# 0_2.net
KiCad netlist of a schematic drawn in EAGLE
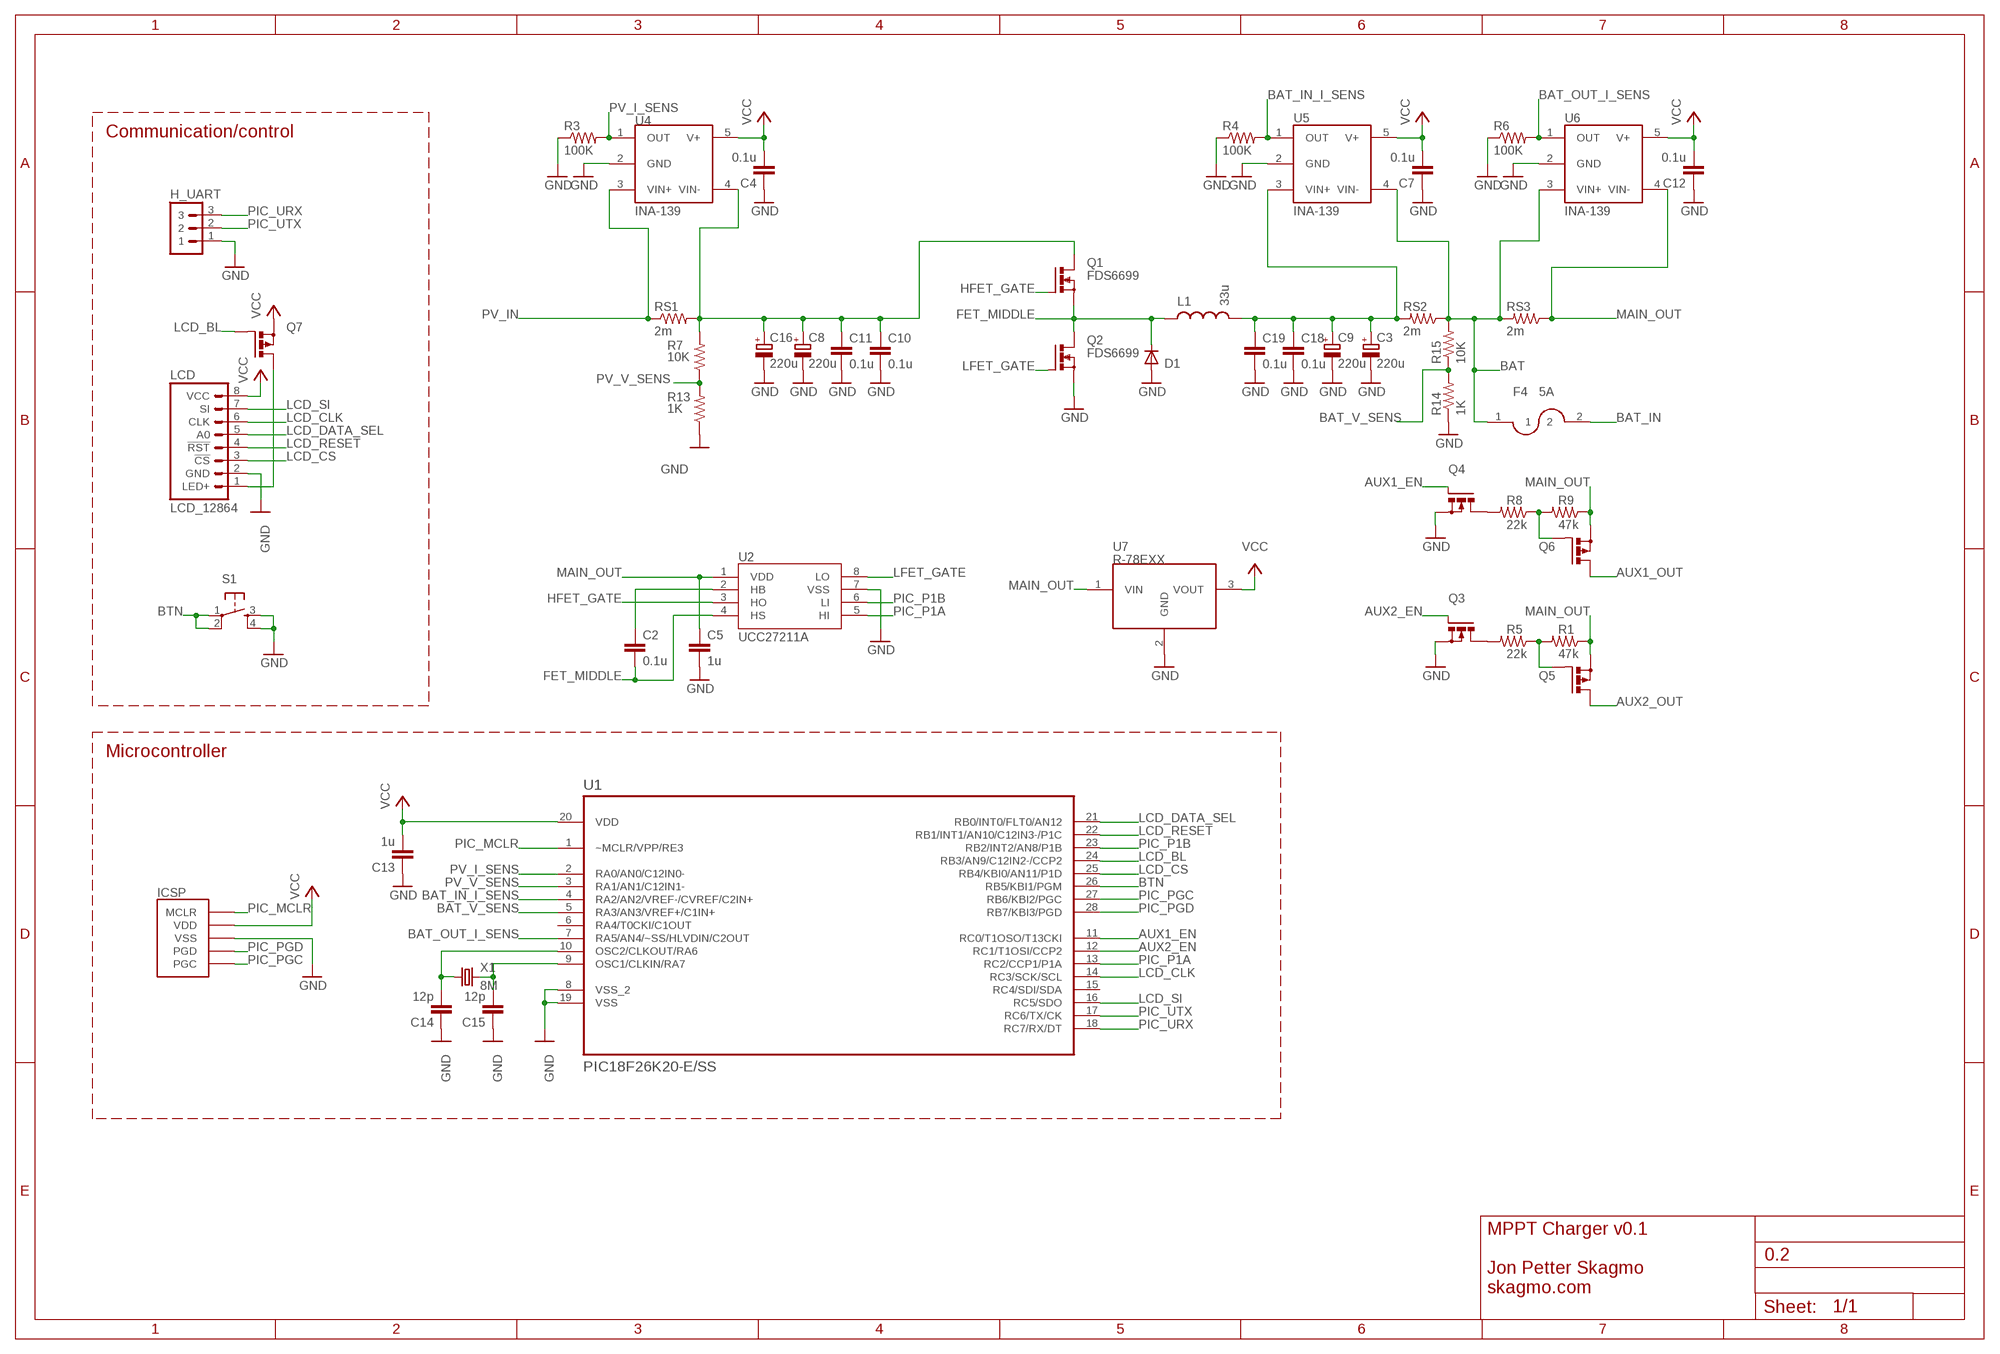
[diagram p0: schematic, sheet 1]

(export (version "E")
  (design (tool "Eeschema 10.0.6"))
  (components
    (comp (ref "C2")
      (value "0.1u")
      (footprint "eagle-import:0603")
      (libsource (lib "eagle-import") (part "CAP0603"))
    )
    (comp (ref "C3")
      (value "220u")
      (footprint "eagle-import:E3,5-8")
      (fields (field (name "PARTNO") "35ZLH220MEFC8X11.5"))
      (libsource (lib "eagle-import") (part "CPOL-EUE3.5-8"))
    )
    (comp (ref "C4")
      (value "0.1u")
      (footprint "eagle-import:0603")
      (libsource (lib "eagle-import") (part "CAP0603"))
    )
    (comp (ref "C5")
      (value "1u")
      (footprint "eagle-import:0603")
      (libsource (lib "eagle-import") (part "CAP0603"))
    )
    (comp (ref "C7")
      (value "0.1u")
      (footprint "eagle-import:0603")
      (libsource (lib "eagle-import") (part "CAP0603"))
    )
    (comp (ref "C8")
      (value "220u")
      (footprint "eagle-import:E3,5-8")
      (fields (field (name "PARTNO") "35ZLH220MEFC8X11.5"))
      (libsource (lib "eagle-import") (part "CPOL-EUE3.5-8"))
    )
    (comp (ref "C9")
      (value "220u")
      (footprint "eagle-import:E3,5-8")
      (fields (field (name "PARTNO") "35ZLH220MEFC8X11.5"))
      (libsource (lib "eagle-import") (part "CPOL-EUE3.5-8"))
    )
    (comp (ref "C10")
      (value "0.1u")
      (footprint "eagle-import:0603")
      (libsource (lib "eagle-import") (part "CAP0603"))
    )
    (comp (ref "C11")
      (value "0.1u")
      (footprint "eagle-import:0603")
      (libsource (lib "eagle-import") (part "CAP0603"))
    )
    (comp (ref "C12")
      (value "0.1u")
      (footprint "eagle-import:0603")
      (libsource (lib "eagle-import") (part "CAP0603"))
    )
    (comp (ref "C13")
      (value "1u")
      (footprint "eagle-import:0603")
      (libsource (lib "eagle-import") (part "CAP0603"))
    )
    (comp (ref "C14")
      (value "12p")
      (footprint "eagle-import:0603")
      (libsource (lib "eagle-import") (part "CAP0603"))
    )
    (comp (ref "C15")
      (value "12p")
      (footprint "eagle-import:0603")
      (libsource (lib "eagle-import") (part "CAP0603"))
    )
    (comp (ref "C16")
      (value "220u")
      (footprint "eagle-import:E3,5-8")
      (fields (field (name "PARTNO") "35ZLH220MEFC8X11.5"))
      (libsource (lib "eagle-import") (part "CPOL-EUE3.5-8"))
    )
    (comp (ref "C18")
      (value "0.1u")
      (footprint "eagle-import:0603")
      (libsource (lib "eagle-import") (part "CAP0603"))
    )
    (comp (ref "C19")
      (value "0.1u")
      (footprint "eagle-import:0603")
      (libsource (lib "eagle-import") (part "CAP0603"))
    )
    (comp (ref "D1")
      (value "DIODESMB")
      (footprint "eagle-import:SMB-DIODE")
      (fields (field (name "PARTNO") "SK54B-LTP"))
      (libsource (lib "eagle-import") (part "DIODESMB"))
    )
    (comp (ref "F4")
      (value "5A")
      (footprint "eagle-import:1206")
      (fields (field (name "PARTNO") "C1T 5"))
      (libsource (lib "eagle-import") (part "FUSE1206"))
    )
    (comp (ref "H_UART")
      (value "H1X3_XH")
      (footprint "eagle-import:CON_B3B-XH-A")
      (fields (field (name "PARTNO") "B3B-XH-A (LF)(SN)(P)"))
      (libsource (lib "eagle-import") (part "H1X3_XH"))
    )
    (comp (ref "ICSP")
      (value "1X5_ICSP")
      (footprint "eagle-import:1X5_2MM")
      (libsource (lib "eagle-import") (part "1X5_ICSP"))
    )
    (comp (ref "L1")
      (value "33u")
      (footprint "eagle-import:IHLP-6767")
      (fields (field (name "PARTNO") "IHLP6767GZER330M11"))
      (libsource (lib "eagle-import") (part "INDUCTORIHLP-6767"))
    )
    (comp (ref "LCD")
      (value "LCD_12864")
      (footprint "eagle-import:LCD_12864")
      (libsource (lib "eagle-import") (part "LCD_12864"))
    )
    (comp (ref "Q1")
      (value "FDS6699")
      (footprint "eagle-import:SO08")
      (fields (field (name "PARTNO") "SI4128DY-T1-GE3"))
      (libsource (lib "eagle-import") (part "PMOSFET_N"))
    )
    (comp (ref "Q2")
      (value "FDS6699")
      (footprint "eagle-import:SO08")
      (fields (field (name "PARTNO") "SI4128DY-T1-GE3"))
      (libsource (lib "eagle-import") (part "PMOSFET_N"))
    )
    (comp (ref "Q3")
      (value "MOSFET_N_SOT23-3")
      (footprint "eagle-import:SOT23-3")
      (fields (field (name "PARTNO") "BSH103,215"))
      (libsource (lib "eagle-import") (part "MOSFET_N_SOT23-3"))
    )
    (comp (ref "Q4")
      (value "MOSFET_N_SOT23-3")
      (footprint "eagle-import:SOT23-3")
      (fields (field (name "PARTNO") "BSH103,215"))
      (libsource (lib "eagle-import") (part "MOSFET_N_SOT23-3"))
    )
    (comp (ref "Q5")
      (value "PMOSFET_P")
      (footprint "eagle-import:SO08")
      (fields (field (name "PARTNO") "FDS6681Z"))
      (libsource (lib "eagle-import") (part "PMOSFET_P"))
    )
    (comp (ref "Q6")
      (value "PMOSFET_P")
      (footprint "eagle-import:SO08")
      (fields (field (name "PARTNO") "FDS6681Z"))
      (libsource (lib "eagle-import") (part "PMOSFET_P"))
    )
    (comp (ref "Q7")
      (value "MOSFET_P_SOT23")
      (footprint "eagle-import:SOT23-3")
      (libsource (lib "eagle-import") (part "MOSFET_P_SOT23"))
    )
    (comp (ref "R1")
      (value "47k")
      (footprint "eagle-import:0603")
      (libsource (lib "eagle-import") (part "RESISTOR0603"))
    )
    (comp (ref "R3")
      (value "100K")
      (footprint "eagle-import:0603")
      (libsource (lib "eagle-import") (part "RESISTOR0603"))
    )
    (comp (ref "R4")
      (value "100K")
      (footprint "eagle-import:0603")
      (libsource (lib "eagle-import") (part "RESISTOR0603"))
    )
    (comp (ref "R5")
      (value "22k")
      (footprint "eagle-import:0603")
      (libsource (lib "eagle-import") (part "RESISTOR0603"))
    )
    (comp (ref "R6")
      (value "100K")
      (footprint "eagle-import:0603")
      (libsource (lib "eagle-import") (part "RESISTOR0603"))
    )
    (comp (ref "R7")
      (value "10K")
      (footprint "eagle-import:0603")
      (libsource (lib "eagle-import") (part "RESISTOR0603"))
    )
    (comp (ref "R8")
      (value "22k")
      (footprint "eagle-import:0603")
      (libsource (lib "eagle-import") (part "RESISTOR0603"))
    )
    (comp (ref "R9")
      (value "47k")
      (footprint "eagle-import:0603")
      (libsource (lib "eagle-import") (part "RESISTOR0603"))
    )
    (comp (ref "R13")
      (value "1K")
      (footprint "eagle-import:0603")
      (libsource (lib "eagle-import") (part "RESISTOR0603"))
    )
    (comp (ref "R14")
      (value "1K")
      (footprint "eagle-import:0603")
      (libsource (lib "eagle-import") (part "RESISTOR0603"))
    )
    (comp (ref "R15")
      (value "10K")
      (footprint "eagle-import:0603")
      (libsource (lib "eagle-import") (part "RESISTOR0603"))
    )
    (comp (ref "RS1")
      (value "2m")
      (footprint "eagle-import:R3225")
      (fields (field (name "PARTNO") "PMR25HZPFV2L00"))
      (libsource (lib "eagle-import") (part "R-US_R3225"))
    )
    (comp (ref "RS2")
      (value "2m")
      (footprint "eagle-import:R3225")
      (fields (field (name "PARTNO") "PMR25HZPFV2L00"))
      (libsource (lib "eagle-import") (part "R-US_R3225"))
    )
    (comp (ref "RS3")
      (value "2m")
      (footprint "eagle-import:R3225")
      (fields (field (name "PARTNO") "PMR25HZPFV2L00"))
      (libsource (lib "eagle-import") (part "R-US_R3225"))
    )
    (comp (ref "S1")
      (value "TAC_SWITCH")
      (footprint "eagle-import:SWITCH_B3FS-1002P")
      (libsource (lib "eagle-import") (part "TAC_SWITCH"))
    )
    (comp (ref "U1")
      (value "PIC18F26K20-E/SS")
      (footprint "eagle-import:SOP65P780X200-28N")
      (fields (field (name "PARTNO") "PIC18F26K22-I/SS"))
      (libsource (lib "eagle-import") (part "PIC18F26K20-E/SS"))
    )
    (comp (ref "U2")
      (value "UCC27211A")
      (footprint "eagle-import:SO08")
      (fields (field (name "PARTNO") "UCC27211D"))
      (libsource (lib "eagle-import") (part "UCC27211A"))
    )
    (comp (ref "U4")
      (value "INA-139")
      (footprint "eagle-import:SOT23-5")
      (fields (field (name "PARTNO") "INA139NA/250"))
      (libsource (lib "eagle-import") (part "INA-169"))
    )
    (comp (ref "U5")
      (value "INA-139")
      (footprint "eagle-import:SOT23-5")
      (fields (field (name "PARTNO") "INA139NA/250"))
      (libsource (lib "eagle-import") (part "INA-169"))
    )
    (comp (ref "U6")
      (value "INA-139")
      (footprint "eagle-import:SOT23-5")
      (fields (field (name "PARTNO") "INA139NA/250"))
      (libsource (lib "eagle-import") (part "INA-169"))
    )
    (comp (ref "U7")
      (value "R-78EXX")
      (footprint "eagle-import:R-78EXX")
      (fields (field (name "PARTNO") "R-78E3.3-0.5"))
      (libsource (lib "eagle-import") (part "R-78EXX"))
    )
    (comp (ref "X1")
      (value "8M")
      (footprint "eagle-import:TXC-7A")
      (fields (field (name "PARTNO") "7A-8.000MAAE-T"))
      (libsource (lib "eagle-import") (part "TXC-7A"))
    )
  )
  (nets
    (net (code "1") (name "/AUX1_EN") (class "Default")
      (node (ref "Q4") (pin "1") (pinfunction "G_1") (pintype "passive"))
      (node (ref "U1") (pin "11") (pinfunction "RC0/T1OSO/T13CKI_11") (pintype "bidirectional"))
    )
    (net (code "2") (name "/AUX1_OUT") (class "Default")
      (node (ref "Q6") (pin "5") (pinfunction "D_5") (pintype "passive"))
      (node (ref "Q6") (pin "6") (pinfunction "D_6") (pintype "passive"))
      (node (ref "Q6") (pin "7") (pinfunction "D_7") (pintype "passive"))
      (node (ref "Q6") (pin "8") (pinfunction "D_8") (pintype "passive"))
    )
    (net (code "3") (name "/AUX2_EN") (class "Default")
      (node (ref "Q3") (pin "1") (pinfunction "G_1") (pintype "passive"))
      (node (ref "U1") (pin "12") (pinfunction "RC1/T1OSI/CCP2_12") (pintype "bidirectional"))
    )
    (net (code "4") (name "/AUX2_OUT") (class "Default")
      (node (ref "Q5") (pin "5") (pinfunction "D_5") (pintype "passive"))
      (node (ref "Q5") (pin "6") (pinfunction "D_6") (pintype "passive"))
      (node (ref "Q5") (pin "7") (pinfunction "D_7") (pintype "passive"))
      (node (ref "Q5") (pin "8") (pinfunction "D_8") (pintype "passive"))
    )
    (net (code "5") (name "/BAT") (class "Default")
      (node (ref "F4") (pin "1") (pinfunction "1_1") (pintype "bidirectional"))
      (node (ref "R15") (pin "2") (pinfunction "2_2") (pintype "passive"))
      (node (ref "RS2") (pin "1") (pinfunction "1_1") (pintype "passive"))
      (node (ref "RS3") (pin "2") (pinfunction "2_2") (pintype "passive"))
      (node (ref "U5") (pin "4") (pinfunction "VIN-_4") (pintype "bidirectional"))
      (node (ref "U6") (pin "3") (pinfunction "VIN+_3") (pintype "bidirectional"))
    )
    (net (code "6") (name "/BAT_IN") (class "Default")
      (node (ref "F4") (pin "2") (pinfunction "2_2") (pintype "bidirectional"))
    )
    (net (code "7") (name "/BAT_IN_I_SENS") (class "Default")
      (node (ref "R4") (pin "2") (pinfunction "2_2") (pintype "passive"))
      (node (ref "U1") (pin "4") (pinfunction "RA2/AN2/VREF-/CVREF/C2IN+_4") (pintype "bidirectional"))
      (node (ref "U5") (pin "1") (pinfunction "OUT_1") (pintype "bidirectional"))
    )
    (net (code "8") (name "/BAT_OUT_I_SENS") (class "Default")
      (node (ref "R6") (pin "2") (pinfunction "2_2") (pintype "passive"))
      (node (ref "U1") (pin "7") (pinfunction "RA5/AN4/~{SS/HLVDIN/C2OUT}_7") (pintype "bidirectional"))
      (node (ref "U6") (pin "1") (pinfunction "OUT_1") (pintype "bidirectional"))
    )
    (net (code "9") (name "/BAT_V_SENS") (class "Default")
      (node (ref "R14") (pin "2") (pinfunction "2_2") (pintype "passive"))
      (node (ref "R15") (pin "1") (pinfunction "1_1") (pintype "passive"))
      (node (ref "U1") (pin "5") (pinfunction "RA3/AN3/VREF+/C1IN+_5") (pintype "bidirectional"))
    )
    (net (code "10") (name "/BTN") (class "Default")
      (node (ref "S1") (pin "1") (pinfunction "1_1") (pintype "passive"))
      (node (ref "S1") (pin "2") (pinfunction "2_2") (pintype "passive"))
      (node (ref "U1") (pin "26") (pinfunction "RB5/KBI1/PGM_26") (pintype "bidirectional"))
    )
    (net (code "11") (name "/FET_MIDDLE") (class "Default")
      (node (ref "C2") (pin "2") (pinfunction "2_2") (pintype "passive"))
      (node (ref "D1") (pin "C") (pinfunction "C_C") (pintype "passive"))
      (node (ref "L1") (pin "P$1") (pinfunction "1_P$1") (pintype "passive"))
      (node (ref "Q1") (pin "1") (pinfunction "S_1") (pintype "passive"))
      (node (ref "Q1") (pin "2") (pinfunction "S_2") (pintype "passive"))
      (node (ref "Q1") (pin "3") (pinfunction "S_3") (pintype "passive"))
      (node (ref "Q2") (pin "5") (pinfunction "D_5") (pintype "passive"))
      (node (ref "Q2") (pin "6") (pinfunction "D_6") (pintype "passive"))
      (node (ref "Q2") (pin "7") (pinfunction "D_7") (pintype "passive"))
      (node (ref "Q2") (pin "8") (pinfunction "D_8") (pintype "passive"))
      (node (ref "U2") (pin "4") (pinfunction "HS_4") (pintype "bidirectional"))
    )
    (net (code "12") (name "/HFET_GATE") (class "Default")
      (node (ref "Q1") (pin "4") (pinfunction "G_4") (pintype "passive"))
      (node (ref "U2") (pin "3") (pinfunction "HO_3") (pintype "bidirectional"))
    )
    (net (code "13") (name "/LCD_BL") (class "Default")
      (node (ref "Q7") (pin "1") (pinfunction "G_1") (pintype "passive"))
      (node (ref "U1") (pin "24") (pinfunction "RB3/AN9/C12IN2-/CCP2_24") (pintype "bidirectional"))
    )
    (net (code "14") (name "/LCD_CLK") (class "Default")
      (node (ref "LCD") (pin "6") (pinfunction "CLK_6") (pintype "passive"))
      (node (ref "U1") (pin "14") (pinfunction "RC3/SCK/SCL_14") (pintype "bidirectional"))
    )
    (net (code "15") (name "/LCD_CS") (class "Default")
      (node (ref "LCD") (pin "3") (pinfunction "~{CS}_3") (pintype "passive"))
      (node (ref "U1") (pin "25") (pinfunction "RB4/KBI0/AN11/P1D_25") (pintype "bidirectional"))
    )
    (net (code "16") (name "/LCD_DATA_SEL") (class "Default")
      (node (ref "LCD") (pin "5") (pinfunction "A0_5") (pintype "passive"))
      (node (ref "U1") (pin "21") (pinfunction "RB0/INT0/FLT0/AN12_21") (pintype "bidirectional"))
    )
    (net (code "17") (name "/LCD_RESET") (class "Default")
      (node (ref "LCD") (pin "4") (pinfunction "~{RST}_4") (pintype "passive"))
      (node (ref "U1") (pin "22") (pinfunction "RB1/INT1/AN10/C12IN3-/P1C_22") (pintype "bidirectional"))
    )
    (net (code "18") (name "/LCD_SI") (class "Default")
      (node (ref "LCD") (pin "7") (pinfunction "SI_7") (pintype "passive"))
      (node (ref "U1") (pin "16") (pinfunction "RC5/SDO_16") (pintype "bidirectional"))
    )
    (net (code "19") (name "/LFET_GATE") (class "Default")
      (node (ref "Q2") (pin "4") (pinfunction "G_4") (pintype "passive"))
      (node (ref "U2") (pin "8") (pinfunction "LO_8") (pintype "bidirectional"))
    )
    (net (code "20") (name "/MAIN_OUT") (class "Default")
      (node (ref "C5") (pin "1") (pinfunction "1_1") (pintype "passive"))
      (node (ref "Q5") (pin "1") (pinfunction "S_1") (pintype "passive"))
      (node (ref "Q5") (pin "2") (pinfunction "S_2") (pintype "passive"))
      (node (ref "Q5") (pin "3") (pinfunction "S_3") (pintype "passive"))
      (node (ref "Q6") (pin "1") (pinfunction "S_1") (pintype "passive"))
      (node (ref "Q6") (pin "2") (pinfunction "S_2") (pintype "passive"))
      (node (ref "Q6") (pin "3") (pinfunction "S_3") (pintype "passive"))
      (node (ref "R1") (pin "1") (pinfunction "1_1") (pintype "passive"))
      (node (ref "R9") (pin "1") (pinfunction "1_1") (pintype "passive"))
      (node (ref "RS3") (pin "1") (pinfunction "1_1") (pintype "passive"))
      (node (ref "U2") (pin "1") (pinfunction "VDD_1") (pintype "bidirectional"))
      (node (ref "U6") (pin "4") (pinfunction "VIN-_4") (pintype "bidirectional"))
      (node (ref "U7") (pin "1") (pinfunction "VIN_1") (pintype "bidirectional"))
    )
    (net (code "21") (name "/PIC_MCLR") (class "Default")
      (node (ref "ICSP") (pin "P$1") (pinfunction "MCLR_P$1") (pintype "bidirectional"))
      (node (ref "U1") (pin "1") (pinfunction "~{MCLR/VPP/RE3}_1") (pintype "input"))
    )
    (net (code "22") (name "/PIC_P1A") (class "Default")
      (node (ref "U1") (pin "13") (pinfunction "RC2/CCP1/P1A_13") (pintype "bidirectional"))
      (node (ref "U2") (pin "5") (pinfunction "HI_5") (pintype "bidirectional"))
    )
    (net (code "23") (name "/PIC_P1B") (class "Default")
      (node (ref "U1") (pin "23") (pinfunction "RB2/INT2/AN8/P1B_23") (pintype "bidirectional"))
      (node (ref "U2") (pin "6") (pinfunction "LI_6") (pintype "bidirectional"))
    )
    (net (code "24") (name "/PIC_PGC") (class "Default")
      (node (ref "ICSP") (pin "P$5") (pinfunction "PGC_P$5") (pintype "bidirectional"))
      (node (ref "U1") (pin "27") (pinfunction "RB6/KBI2/PGC_27") (pintype "bidirectional"))
    )
    (net (code "25") (name "/PIC_PGD") (class "Default")
      (node (ref "ICSP") (pin "P$4") (pinfunction "PGD_P$4") (pintype "bidirectional"))
      (node (ref "U1") (pin "28") (pinfunction "RB7/KBI3/PGD_28") (pintype "bidirectional"))
    )
    (net (code "26") (name "/PIC_URX") (class "Default")
      (node (ref "H_UART") (pin "3") (pinfunction "3_3") (pintype "passive"))
      (node (ref "U1") (pin "18") (pinfunction "RC7/RX/DT_18") (pintype "bidirectional"))
    )
    (net (code "27") (name "/PIC_UTX") (class "Default")
      (node (ref "H_UART") (pin "2") (pinfunction "2_2") (pintype "passive"))
      (node (ref "U1") (pin "17") (pinfunction "RC6/TX/CK_17") (pintype "bidirectional"))
    )
    (net (code "28") (name "/PV_IN") (class "Default")
      (node (ref "RS1") (pin "1") (pinfunction "1_1") (pintype "passive"))
      (node (ref "U4") (pin "3") (pinfunction "VIN+_3") (pintype "bidirectional"))
    )
    (net (code "29") (name "/PV_I_SENS") (class "Default")
      (node (ref "R3") (pin "2") (pinfunction "2_2") (pintype "passive"))
      (node (ref "U1") (pin "2") (pinfunction "RA0/AN0/C12IN0-_2") (pintype "bidirectional"))
      (node (ref "U4") (pin "1") (pinfunction "OUT_1") (pintype "bidirectional"))
    )
    (net (code "30") (name "/PV_V_SENS") (class "Default")
      (node (ref "R13") (pin "2") (pinfunction "2_2") (pintype "passive"))
      (node (ref "R7") (pin "1") (pinfunction "1_1") (pintype "passive"))
      (node (ref "U1") (pin "3") (pinfunction "RA1/AN1/C12IN1-_3") (pintype "bidirectional"))
    )
    (net (code "31") (name "GND") (class "Default")
      (node (ref "C10") (pin "2") (pinfunction "2_2") (pintype "passive"))
      (node (ref "C11") (pin "2") (pinfunction "2_2") (pintype "passive"))
      (node (ref "C12") (pin "1") (pinfunction "1_1") (pintype "passive"))
      (node (ref "C13") (pin "1") (pinfunction "1_1") (pintype "passive"))
      (node (ref "C14") (pin "1") (pinfunction "1_1") (pintype "passive"))
      (node (ref "C15") (pin "1") (pinfunction "1_1") (pintype "passive"))
      (node (ref "C16") (pin "-") (pinfunction "-_-") (pintype "passive"))
      (node (ref "C18") (pin "2") (pinfunction "2_2") (pintype "passive"))
      (node (ref "C19") (pin "2") (pinfunction "2_2") (pintype "passive"))
      (node (ref "C3") (pin "-") (pinfunction "-_-") (pintype "passive"))
      (node (ref "C4") (pin "1") (pinfunction "1_1") (pintype "passive"))
      (node (ref "C5") (pin "2") (pinfunction "2_2") (pintype "passive"))
      (node (ref "C7") (pin "1") (pinfunction "1_1") (pintype "passive"))
      (node (ref "C8") (pin "-") (pinfunction "-_-") (pintype "passive"))
      (node (ref "C9") (pin "-") (pinfunction "-_-") (pintype "passive"))
      (node (ref "D1") (pin "A") (pinfunction "A_A") (pintype "passive"))
      (node (ref "H_UART") (pin "1") (pinfunction "1_1") (pintype "passive"))
      (node (ref "ICSP") (pin "P$3") (pinfunction "VSS_P$3") (pintype "power_in"))
      (node (ref "LCD") (pin "2") (pinfunction "GND_2") (pintype "passive"))
      (node (ref "Q2") (pin "1") (pinfunction "S_1") (pintype "passive"))
      (node (ref "Q2") (pin "2") (pinfunction "S_2") (pintype "passive"))
      (node (ref "Q2") (pin "3") (pinfunction "S_3") (pintype "passive"))
      (node (ref "Q3") (pin "2") (pinfunction "S_2") (pintype "passive"))
      (node (ref "Q4") (pin "2") (pinfunction "S_2") (pintype "passive"))
      (node (ref "R13") (pin "1") (pinfunction "1_1") (pintype "passive"))
      (node (ref "R14") (pin "1") (pinfunction "1_1") (pintype "passive"))
      (node (ref "R3") (pin "1") (pinfunction "1_1") (pintype "passive"))
      (node (ref "R4") (pin "1") (pinfunction "1_1") (pintype "passive"))
      (node (ref "R6") (pin "1") (pinfunction "1_1") (pintype "passive"))
      (node (ref "S1") (pin "3") (pinfunction "3_3") (pintype "passive"))
      (node (ref "S1") (pin "4") (pinfunction "4_4") (pintype "passive"))
      (node (ref "U1") (pin "19") (pinfunction "VSS_19") (pintype "power_in"))
      (node (ref "U1") (pin "8") (pinfunction "VSS_2_8") (pintype "power_in"))
      (node (ref "U2") (pin "7") (pinfunction "VSS_7") (pintype "bidirectional"))
      (node (ref "U4") (pin "2") (pinfunction "GND_2") (pintype "bidirectional"))
      (node (ref "U5") (pin "2") (pinfunction "GND_2") (pintype "bidirectional"))
      (node (ref "U6") (pin "2") (pinfunction "GND_2") (pintype "bidirectional"))
      (node (ref "U7") (pin "2") (pinfunction "GND_2") (pintype "bidirectional"))
    )
    (net (code "32") (name "Net-(L1-2)") (class "Default")
      (node (ref "C18") (pin "1") (pinfunction "1_1") (pintype "passive"))
      (node (ref "C19") (pin "1") (pinfunction "1_1") (pintype "passive"))
      (node (ref "C3") (pin "+") (pinfunction "+_+") (pintype "passive"))
      (node (ref "C9") (pin "+") (pinfunction "+_+") (pintype "passive"))
      (node (ref "L1") (pin "P$2") (pinfunction "2_P$2") (pintype "passive"))
      (node (ref "RS2") (pin "2") (pinfunction "2_2") (pintype "passive"))
      (node (ref "U5") (pin "3") (pinfunction "VIN+_3") (pintype "bidirectional"))
    )
    (net (code "33") (name "Net-(LCD-LED+)") (class "Default")
      (node (ref "LCD") (pin "1") (pinfunction "LED+_1") (pintype "passive"))
      (node (ref "Q7") (pin "3") (pinfunction "D_3") (pintype "passive"))
    )
    (net (code "34") (name "Net-(Q3-D)") (class "Default")
      (node (ref "Q3") (pin "3") (pinfunction "D_3") (pintype "passive"))
      (node (ref "R5") (pin "2") (pinfunction "2_2") (pintype "passive"))
    )
    (net (code "35") (name "Net-(Q4-D)") (class "Default")
      (node (ref "Q4") (pin "3") (pinfunction "D_3") (pintype "passive"))
      (node (ref "R8") (pin "2") (pinfunction "2_2") (pintype "passive"))
    )
    (net (code "36") (name "Net-(Q5-G)") (class "Default")
      (node (ref "Q5") (pin "4") (pinfunction "G_4") (pintype "passive"))
      (node (ref "R1") (pin "2") (pinfunction "2_2") (pintype "passive"))
      (node (ref "R5") (pin "1") (pinfunction "1_1") (pintype "passive"))
    )
    (net (code "37") (name "Net-(Q6-G)") (class "Default")
      (node (ref "Q6") (pin "4") (pinfunction "G_4") (pintype "passive"))
      (node (ref "R8") (pin "1") (pinfunction "1_1") (pintype "passive"))
      (node (ref "R9") (pin "2") (pinfunction "2_2") (pintype "passive"))
    )
    (net (code "38") (name "Net-(U1-OSC1{slash}CLKIN{slash}RA7)") (class "Default")
      (node (ref "C15") (pin "2") (pinfunction "2_2") (pintype "passive"))
      (node (ref "U1") (pin "9") (pinfunction "OSC1/CLKIN/RA7_9") (pintype "bidirectional"))
      (node (ref "X1") (pin "2") (pinfunction "2_2") (pintype "passive"))
    )
    (net (code "39") (name "Net-(U1-OSC2{slash}CLKOUT{slash}RA6)") (class "Default")
      (node (ref "C14") (pin "2") (pinfunction "2_2") (pintype "passive"))
      (node (ref "U1") (pin "10") (pinfunction "OSC2/CLKOUT/RA6_10") (pintype "bidirectional"))
      (node (ref "X1") (pin "1") (pinfunction "1_1") (pintype "passive"))
    )
    (net (code "40") (name "Net-(U2-HB)") (class "Default")
      (node (ref "C2") (pin "1") (pinfunction "1_1") (pintype "passive"))
      (node (ref "U2") (pin "2") (pinfunction "HB_2") (pintype "bidirectional"))
    )
    (net (code "41") (name "Net-(U4-VIN-)") (class "Default")
      (node (ref "C10") (pin "1") (pinfunction "1_1") (pintype "passive"))
      (node (ref "C11") (pin "1") (pinfunction "1_1") (pintype "passive"))
      (node (ref "C16") (pin "+") (pinfunction "+_+") (pintype "passive"))
      (node (ref "C8") (pin "+") (pinfunction "+_+") (pintype "passive"))
      (node (ref "Q1") (pin "5") (pinfunction "D_5") (pintype "passive"))
      (node (ref "Q1") (pin "6") (pinfunction "D_6") (pintype "passive"))
      (node (ref "Q1") (pin "7") (pinfunction "D_7") (pintype "passive"))
      (node (ref "Q1") (pin "8") (pinfunction "D_8") (pintype "passive"))
      (node (ref "R7") (pin "2") (pinfunction "2_2") (pintype "passive"))
      (node (ref "RS1") (pin "2") (pinfunction "2_2") (pintype "passive"))
      (node (ref "U4") (pin "4") (pinfunction "VIN-_4") (pintype "bidirectional"))
    )
    (net (code "42") (name "VCC") (class "Default")
      (node (ref "C12") (pin "2") (pinfunction "2_2") (pintype "passive"))
      (node (ref "C13") (pin "2") (pinfunction "2_2") (pintype "passive"))
      (node (ref "C4") (pin "2") (pinfunction "2_2") (pintype "passive"))
      (node (ref "C7") (pin "2") (pinfunction "2_2") (pintype "passive"))
      (node (ref "ICSP") (pin "P$2") (pinfunction "VDD_P$2") (pintype "power_in"))
      (node (ref "LCD") (pin "8") (pinfunction "VCC_8") (pintype "passive"))
      (node (ref "Q7") (pin "2") (pinfunction "S_2") (pintype "passive"))
      (node (ref "U1") (pin "20") (pinfunction "VDD_20") (pintype "power_in"))
      (node (ref "U4") (pin "5") (pinfunction "V+_5") (pintype "bidirectional"))
      (node (ref "U5") (pin "5") (pinfunction "V+_5") (pintype "bidirectional"))
      (node (ref "U6") (pin "5") (pinfunction "V+_5") (pintype "bidirectional"))
      (node (ref "U7") (pin "3") (pinfunction "VOUT_3") (pintype "bidirectional"))
    )
    (net (code "43") (name "unconnected-(U1-RA4{slash}T0CKI{slash}C1OUT-Pad6)") (class "Default")
      (node (ref "U1") (pin "6") (pinfunction "RA4/T0CKI/C1OUT_6") (pintype "bidirectional"))
    )
    (net (code "44") (name "unconnected-(U1-RC4{slash}SDI{slash}SDA-Pad15)") (class "Default")
      (node (ref "U1") (pin "15") (pinfunction "RC4/SDI/SDA_15") (pintype "bidirectional"))
    )
  )
)
